# 780-00055_rev2_Pg3_SCH_NRES_Temp_Meas_8-.net
KiCad netlist of a schematic drawn in Altium Designer
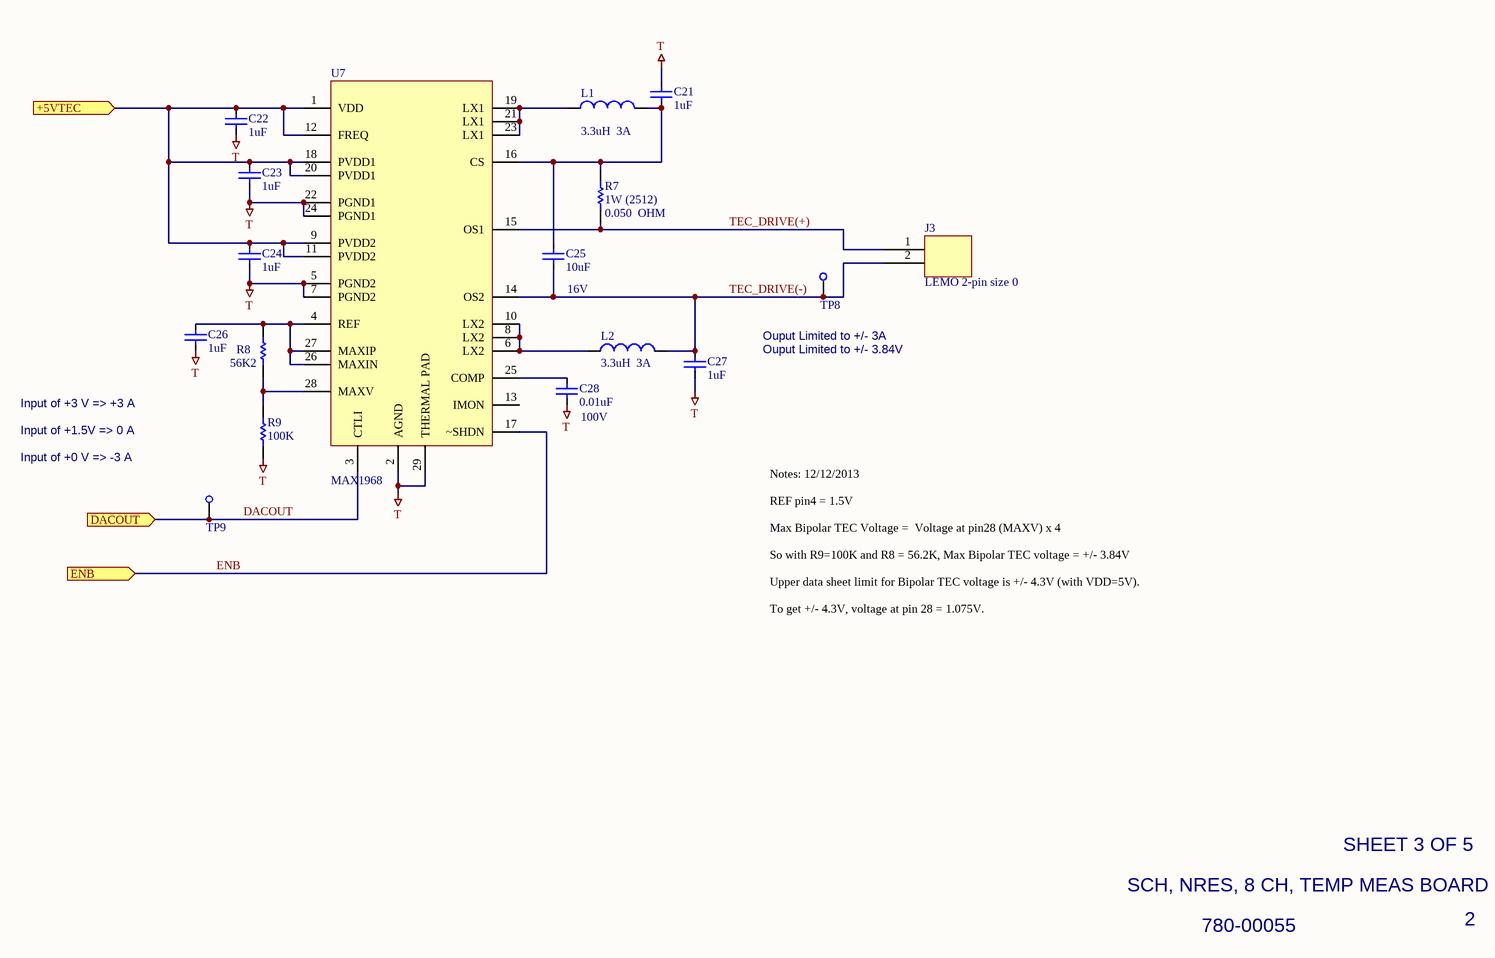
[diagram p0: 780-00055, rev2, Pg3, SCH, NRES Temp Meas, 8-Chan RTD .SchDoc]

(export (version "E")
  (design (tool "Eeschema 10.0.6"))
  (components
    (comp (ref "C21")
      (value "1uF")
      (footprint "SMD_0805")
      (description "Capacitor")
      (fields (field (name "Comment") "Cap SMD"))
      (libsource (lib "Richs Schematic Components") (part "Cap SMD"))
    )
    (comp (ref "C22")
      (value "1uF")
      (footprint "SMD_0805")
      (description "Capacitor")
      (fields (field (name "Comment") "Cap SMD"))
      (libsource (lib "Richs Schematic Components") (part "Cap SMD"))
    )
    (comp (ref "C23")
      (value "1uF")
      (footprint "SMD_0805")
      (description "Capacitor")
      (fields (field (name "Comment") "Cap SMD"))
      (libsource (lib "Richs Schematic Components") (part "Cap SMD"))
    )
    (comp (ref "C24")
      (value "1uF")
      (footprint "SMD_0805")
      (description "Capacitor")
      (fields (field (name "Comment") "Cap SMD"))
      (libsource (lib "Richs Schematic Components") (part "Cap SMD"))
    )
    (comp (ref "C25")
      (value "16V")
      (footprint "SMD_0805")
      (description "Capacitor")
      (fields (field (name "ALTIUM_VALUE") "10uF"))
      (libsource (lib "Richs Schematic Components") (part "Cap SMD"))
    )
    (comp (ref "C26")
      (value "1uF")
      (footprint "SMD_0805")
      (description "Capacitor")
      (fields (field (name "Comment") "Cap SMD"))
      (libsource (lib "Richs Schematic Components") (part "Cap SMD"))
    )
    (comp (ref "C27")
      (value "1uF")
      (footprint "SMD_0805")
      (description "Capacitor")
      (fields (field (name "Comment") "Cap SMD"))
      (libsource (lib "Richs Schematic Components") (part "Cap SMD"))
    )
    (comp (ref "C28")
      (value "100V")
      (footprint "SMD_0805")
      (description "Capacitor")
      (fields (field (name "MANUFACTURER") "Johanson") (field (name "ALTIUM_VALUE") "0.01uF"))
      (libsource (lib "Richs Schematic Components") (part "Cap SMD"))
    )
    (comp (ref "J3")
      (value "LEMO 2-pin size 0")
      (footprint "LEMO Size 0, 2-pin PCB")
      (libsource (lib "Richs Schematic Components") (part "LEMO Size 0, 2 pin, PCB"))
    )
    (comp (ref "L1")
      (value "3.3uH  3A")
      (footprint "SMT Inductor 7 x 7mm")
      (description "Inductor")
      (fields (field (name "MANUFACTURER") "Coiltronics") (field (name "Comment") "513-1481-2-ND"))
      (libsource (lib "Richs Schematic Components") (part "Inductor SMD 7 x 7mm"))
    )
    (comp (ref "L2")
      (value "3.3uH  3A")
      (footprint "SMT Inductor 7 x 7mm")
      (description "Inductor")
      (fields (field (name "MANUFACTURER") "Coiltronics") (field (name "Comment") "513-1481-2-ND"))
      (libsource (lib "Richs Schematic Components") (part "Inductor SMD 7 x 7mm"))
    )
    (comp (ref "R7")
      (value "1W (2512)")
      (footprint "6332[2512]")
      (fields (field (name "MANUFACTURER") "Panasonic") (field (name "ALTIUM_VALUE") "0.050  OHM"))
      (libsource (lib "Richs Schematic Components") (part "Res SMD"))
    )
    (comp (ref "R8")
      (value "56K2")
      (footprint "SMD_0805")
      (description "Resistor 0805")
      (fields (field (name "MANUFACTURER") "Vishay/Dale") (field (name "Comment") "Res 0805"))
      (libsource (lib "Richs Schematic Components") (part "Res SMD"))
    )
    (comp (ref "R9")
      (value "100K")
      (footprint "SMD_0805")
      (description "Resistor 0805")
      (fields (field (name "MANUFACTURER") "Vishay/Dale") (field (name "Comment") "Res 0805"))
      (libsource (lib "Richs Schematic Components") (part "Res SMD"))
    )
    (comp (ref "TP8")
      (value "Test point")
      (footprint "Protel 99SE BANKS PCB:PAD_80D_052H")
      (description "Test Point")
      (fields (field (name "MANUFACTURER") "Keystone"))
      (libsource (lib "Richs Schematic Components") (part "Test point"))
    )
    (comp (ref "TP9")
      (value "Test point")
      (footprint "Protel 99SE BANKS PCB:PAD_80D_052H")
      (description "Test Point")
      (fields (field (name "MANUFACTURER") "Keystone"))
      (libsource (lib "Richs Schematic Components") (part "Test point"))
    )
    (comp (ref "U7")
      (value "MAX1968")
      (footprint "TSSOP28 Exposed Pad")
      (description "TEC Driver +/- 3A")
      (fields (field (name "MANUFACTURER") "Maxim"))
      (libsource (lib "Richs Schematic Components") (part "MAX1968"))
    )
  )
  (nets
    (net (code "1") (name "/+5VTEC") (class "Default")
      (node (ref "C22") (pin "2") (pinfunction "2_2") (pintype "passive"))
      (node (ref "C23") (pin "2") (pinfunction "2_2") (pintype "passive"))
      (node (ref "C24") (pin "2") (pinfunction "2_2") (pintype "passive"))
      (node (ref "U7") (pin "1") (pinfunction "VDD_1") (pintype "passive"))
      (node (ref "U7") (pin "11") (pinfunction "PVDD2_11") (pintype "passive"))
      (node (ref "U7") (pin "12") (pinfunction "FREQ_12") (pintype "passive"))
      (node (ref "U7") (pin "18") (pinfunction "PVDD1_18") (pintype "passive"))
      (node (ref "U7") (pin "20") (pinfunction "PVDD1_20") (pintype "passive"))
      (node (ref "U7") (pin "9") (pinfunction "PVDD2_9") (pintype "passive"))
    )
    (net (code "2") (name "/DACOUT") (class "Default")
      (node (ref "TP9") (pin "1") (pinfunction "TP_1") (pintype "passive"))
      (node (ref "U7") (pin "3") (pinfunction "CTLI_3") (pintype "passive"))
    )
    (net (code "3") (name "/ENB") (class "Default")
      (node (ref "U7") (pin "17") (pinfunction "~SHDN_17") (pintype "passive"))
    )
    (net (code "4") (name "/TEC_DRIVE(+)") (class "Default")
      (node (ref "J3") (pin "1") (pinfunction "S29_1") (pintype "passive"))
      (node (ref "R7") (pin "1") (pinfunction "1_1") (pintype "passive"))
      (node (ref "U7") (pin "15") (pinfunction "OS1_15") (pintype "passive"))
    )
    (net (code "5") (name "/TEC_DRIVE(-)") (class "Default")
      (node (ref "C25") (pin "1") (pinfunction "1_1") (pintype "passive"))
      (node (ref "C27") (pin "2") (pinfunction "2_2") (pintype "passive"))
      (node (ref "J3") (pin "2") (pinfunction "S30_2") (pintype "passive"))
      (node (ref "L2") (pin "2") (pinfunction "2_2") (pintype "passive"))
      (node (ref "TP8") (pin "1") (pinfunction "TP_1") (pintype "passive"))
      (node (ref "U7") (pin "14") (pinfunction "OS2_14") (pintype "passive"))
    )
    (net (code "6") (name "Net-(L1-Pad1)") (class "Default")
      (node (ref "L1") (pin "1") (pinfunction "1_1") (pintype "passive"))
      (node (ref "U7") (pin "19") (pinfunction "LX1_19") (pintype "passive"))
      (node (ref "U7") (pin "21") (pinfunction "LX1_21") (pintype "passive"))
      (node (ref "U7") (pin "23") (pinfunction "LX1_23") (pintype "passive"))
    )
    (net (code "7") (name "Net-(L2-Pad1)") (class "Default")
      (node (ref "L2") (pin "1") (pinfunction "1_1") (pintype "passive"))
      (node (ref "U7") (pin "10") (pinfunction "LX2_10") (pintype "passive"))
      (node (ref "U7") (pin "6") (pinfunction "LX2_6") (pintype "passive"))
      (node (ref "U7") (pin "8") (pinfunction "LX2_8") (pintype "passive"))
    )
    (net (code "8") (name "Net-(U7-COMP)") (class "Default")
      (node (ref "C28") (pin "2") (pinfunction "2_2") (pintype "passive"))
      (node (ref "U7") (pin "25") (pinfunction "COMP_25") (pintype "passive"))
    )
    (net (code "9") (name "Net-(U7-CS)") (class "Default")
      (node (ref "C21") (pin "1") (pinfunction "1_1") (pintype "passive"))
      (node (ref "C25") (pin "2") (pinfunction "2_2") (pintype "passive"))
      (node (ref "L1") (pin "2") (pinfunction "2_2") (pintype "passive"))
      (node (ref "R7") (pin "2") (pinfunction "2_2") (pintype "passive"))
      (node (ref "U7") (pin "16") (pinfunction "CS_16") (pintype "passive"))
    )
    (net (code "10") (name "Net-(U7-MAXIN)") (class "Default")
      (node (ref "C26") (pin "2") (pinfunction "2_2") (pintype "passive"))
      (node (ref "R8") (pin "2") (pinfunction "2_2") (pintype "passive"))
      (node (ref "U7") (pin "26") (pinfunction "MAXIN_26") (pintype "passive"))
      (node (ref "U7") (pin "27") (pinfunction "MAXIP_27") (pintype "passive"))
      (node (ref "U7") (pin "4") (pinfunction "REF_4") (pintype "passive"))
    )
    (net (code "11") (name "Net-(U7-MAXV)") (class "Default")
      (node (ref "R8") (pin "1") (pinfunction "1_1") (pintype "passive"))
      (node (ref "R9") (pin "2") (pinfunction "2_2") (pintype "passive"))
      (node (ref "U7") (pin "28") (pinfunction "MAXV_28") (pintype "passive"))
    )
    (net (code "12") (name "T") (class "Default")
      (node (ref "C21") (pin "2") (pinfunction "2_2") (pintype "passive"))
      (node (ref "C22") (pin "1") (pinfunction "1_1") (pintype "passive"))
      (node (ref "C23") (pin "1") (pinfunction "1_1") (pintype "passive"))
      (node (ref "C24") (pin "1") (pinfunction "1_1") (pintype "passive"))
      (node (ref "C26") (pin "1") (pinfunction "1_1") (pintype "passive"))
      (node (ref "C27") (pin "1") (pinfunction "1_1") (pintype "passive"))
      (node (ref "C28") (pin "1") (pinfunction "1_1") (pintype "passive"))
      (node (ref "R9") (pin "1") (pinfunction "1_1") (pintype "passive"))
      (node (ref "U7") (pin "2") (pinfunction "AGND_2") (pintype "passive"))
      (node (ref "U7") (pin "22") (pinfunction "PGND1_22") (pintype "passive"))
      (node (ref "U7") (pin "24") (pinfunction "PGND1_24") (pintype "passive"))
      (node (ref "U7") (pin "29") (pinfunction "THERMAL_PAD_29") (pintype "passive"))
      (node (ref "U7") (pin "5") (pinfunction "PGND2_5") (pintype "passive"))
      (node (ref "U7") (pin "7") (pinfunction "PGND2_7") (pintype "passive"))
    )
    (net (code "13") (name "unconnected-(U7-IMON-Pad13)") (class "Default")
      (node (ref "U7") (pin "13") (pinfunction "IMON_13") (pintype "passive"))
    )
  )
)
